# differential_op_amps.net
KiCad netlist of a schematic drawn in Altium Designer
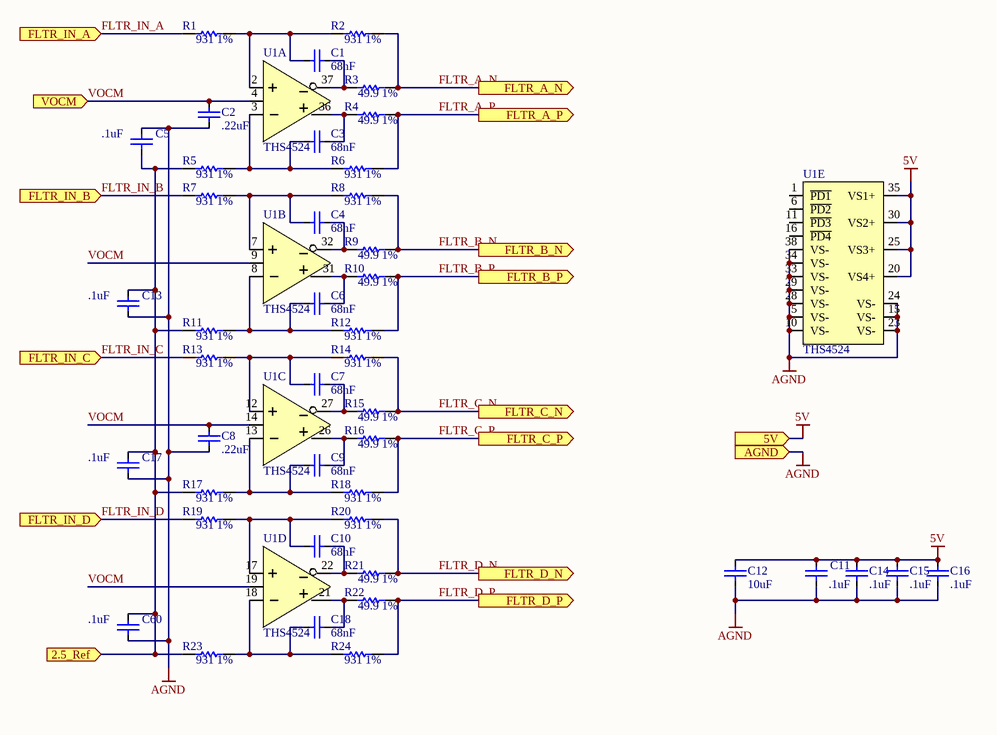
[diagram p0: differential_op_amps.SchDoc]

(export (version "E")
  (design (tool "Eeschema 10.0.6"))
  (components
    (comp (ref "C1")
      (value "68nF")
      (footprint "0603 (1608)")
      (fields
        (field (name "MANUFACTURER") "TDK")
        (field (name "PART NO.") "445-5096-1-ND")
        (field (name "Comment") "Capacitor")
      )
      (libsource (lib "SMT Chip") (part "Capacitor"))
    )
    (comp (ref "C2")
      (value ".22uF")
      (footprint "0603 (1608)")
      (fields
        (field (name "MANUFACTURER") "TDK")
        (field (name "PART NO.") "445-1318-1-ND")
        (field (name "Comment") "Capacitor")
      )
      (libsource (lib "SMT Chip") (part "Capacitor"))
    )
    (comp (ref "C3")
      (value "68nF")
      (footprint "0603 (1608)")
      (fields
        (field (name "MANUFACTURER") "TDK")
        (field (name "PART NO.") "445-5096-1-ND")
        (field (name "Comment") "Capacitor")
      )
      (libsource (lib "SMT Chip") (part "Capacitor"))
    )
    (comp (ref "C4")
      (value "68nF")
      (footprint "0603 (1608)")
      (fields
        (field (name "MANUFACTURER") "TDK")
        (field (name "PART NO.") "445-5096-1-ND")
        (field (name "Comment") "Capacitor")
      )
      (libsource (lib "SMT Chip") (part "Capacitor"))
    )
    (comp (ref "C5")
      (value ".1uF")
      (footprint "0603 (1608)")
      (fields
        (field (name "MANUFACTURER") "Murata")
        (field (name "PART NO.") "490-1524-1-ND")
        (field (name "Comment") "Capacitor")
      )
      (libsource (lib "SMT Chip") (part "Capacitor"))
    )
    (comp (ref "C6")
      (value "68nF")
      (footprint "0603 (1608)")
      (fields
        (field (name "MANUFACTURER") "TDK")
        (field (name "PART NO.") "445-5096-1-ND")
        (field (name "Comment") "Capacitor")
      )
      (libsource (lib "SMT Chip") (part "Capacitor"))
    )
    (comp (ref "C7")
      (value "68nF")
      (footprint "0603 (1608)")
      (fields
        (field (name "MANUFACTURER") "TDK")
        (field (name "PART NO.") "445-5096-1-ND")
        (field (name "Comment") "Capacitor")
      )
      (libsource (lib "SMT Chip") (part "Capacitor"))
    )
    (comp (ref "C8")
      (value ".22uF")
      (footprint "0603 (1608)")
      (fields
        (field (name "MANUFACTURER") "TDK")
        (field (name "PART NO.") "445-1318-1-ND")
        (field (name "Comment") "Capacitor")
      )
      (libsource (lib "SMT Chip") (part "Capacitor"))
    )
    (comp (ref "C9")
      (value "68nF")
      (footprint "0603 (1608)")
      (fields
        (field (name "MANUFACTURER") "TDK")
        (field (name "PART NO.") "445-5096-1-ND")
        (field (name "Comment") "Capacitor")
      )
      (libsource (lib "SMT Chip") (part "Capacitor"))
    )
    (comp (ref "C10")
      (value "68nF")
      (footprint "0603 (1608)")
      (fields
        (field (name "MANUFACTURER") "TDK")
        (field (name "PART NO.") "445-5096-1-ND")
        (field (name "Comment") "Capacitor")
      )
      (libsource (lib "SMT Chip") (part "Capacitor"))
    )
    (comp (ref "C11")
      (value ".1uF")
      (footprint "0603 (1608)")
      (fields
        (field (name "MANUFACTURER") "Murata")
        (field (name "PART NO.") "490-1524-1-ND")
        (field (name "Comment") "Capacitor")
      )
      (libsource (lib "SMT Chip") (part "Capacitor"))
    )
    (comp (ref "C12")
      (value "10uF")
      (footprint "0603 (1608)")
      (fields
        (field (name "MANUFACTURER") "Taiyo Yuden")
        (field (name "PART NO.") "587-2562-1-ND")
        (field (name "TOLERANCE") "20%")
      )
      (libsource (lib "SMT Chip") (part "Capacitor"))
    )
    (comp (ref "C13")
      (value ".1uF")
      (footprint "0603 (1608)")
      (fields
        (field (name "MANUFACTURER") "Murata")
        (field (name "PART NO.") "490-1524-1-ND")
        (field (name "Comment") "Capacitor")
      )
      (libsource (lib "SMT Chip") (part "Capacitor"))
    )
    (comp (ref "C14")
      (value ".1uF")
      (footprint "0603 (1608)")
      (fields
        (field (name "MANUFACTURER") "Murata")
        (field (name "PART NO.") "490-1524-1-ND")
        (field (name "Comment") "Capacitor")
      )
      (libsource (lib "SMT Chip") (part "Capacitor"))
    )
    (comp (ref "C15")
      (value ".1uF")
      (footprint "0603 (1608)")
      (fields
        (field (name "MANUFACTURER") "Murata")
        (field (name "PART NO.") "490-1524-1-ND")
        (field (name "Comment") "Capacitor")
      )
      (libsource (lib "SMT Chip") (part "Capacitor"))
    )
    (comp (ref "C16")
      (value ".1uF")
      (footprint "0603 (1608)")
      (fields
        (field (name "MANUFACTURER") "Murata")
        (field (name "PART NO.") "490-1524-1-ND")
        (field (name "Comment") "Capacitor")
      )
      (libsource (lib "SMT Chip") (part "Capacitor"))
    )
    (comp (ref "C17")
      (value ".1uF")
      (footprint "0603 (1608)")
      (fields
        (field (name "MANUFACTURER") "Murata")
        (field (name "PART NO.") "490-1524-1-ND")
        (field (name "Comment") "Capacitor")
      )
      (libsource (lib "SMT Chip") (part "Capacitor"))
    )
    (comp (ref "C18")
      (value "68nF")
      (footprint "0603 (1608)")
      (fields
        (field (name "MANUFACTURER") "TDK")
        (field (name "PART NO.") "445-5096-1-ND")
        (field (name "Comment") "Capacitor")
      )
      (libsource (lib "SMT Chip") (part "Capacitor"))
    )
    (comp (ref "C60")
      (value ".1uF")
      (footprint "0603 (1608)")
      (fields
        (field (name "MANUFACTURER") "Murata")
        (field (name "PART NO.") "490-1524-1-ND")
        (field (name "Comment") "Capacitor")
      )
      (libsource (lib "SMT Chip") (part "Capacitor"))
    )
    (comp (ref "R1")
      (value "931 1%")
      (footprint "0603 (1608)")
      (description "Resistor")
      (fields (field (name "PART NO.") "P931HCT-ND"))
      (libsource (lib "Miscellaneous Devices") (part "Res1"))
    )
    (comp (ref "R2")
      (value "931 1%")
      (footprint "0603 (1608)")
      (description "Resistor")
      (fields (field (name "PART NO.") "P931HCT-ND"))
      (libsource (lib "Miscellaneous Devices") (part "Res1"))
    )
    (comp (ref "R3")
      (value "49.9 1%")
      (footprint "0603 (1608)")
      (description "Resistor")
      (fields (field (name "PART NO.") "P49.9HCT-ND") (field (name "Comment") "931 1%"))
      (libsource (lib "Miscellaneous Devices") (part "Res1"))
    )
    (comp (ref "R4")
      (value "49.9 1%")
      (footprint "0603 (1608)")
      (description "Resistor")
      (fields (field (name "PART NO.") "P49.9HCT-ND") (field (name "Comment") "931 1%"))
      (libsource (lib "Miscellaneous Devices") (part "Res1"))
    )
    (comp (ref "R5")
      (value "931 1%")
      (footprint "0603 (1608)")
      (description "Resistor")
      (fields (field (name "PART NO.") "P931HCT-ND"))
      (libsource (lib "Miscellaneous Devices") (part "Res1"))
    )
    (comp (ref "R6")
      (value "931 1%")
      (footprint "0603 (1608)")
      (description "Resistor")
      (fields (field (name "PART NO.") "P931HCT-ND"))
      (libsource (lib "Miscellaneous Devices") (part "Res1"))
    )
    (comp (ref "R7")
      (value "931 1%")
      (footprint "0603 (1608)")
      (description "Resistor")
      (fields (field (name "PART NO.") "P931HCT-ND"))
      (libsource (lib "Miscellaneous Devices") (part "Res1"))
    )
    (comp (ref "R8")
      (value "931 1%")
      (footprint "0603 (1608)")
      (description "Resistor")
      (fields (field (name "PART NO.") "P931HCT-ND"))
      (libsource (lib "Miscellaneous Devices") (part "Res1"))
    )
    (comp (ref "R9")
      (value "49.9 1%")
      (footprint "0603 (1608)")
      (description "Resistor")
      (fields (field (name "PART NO.") "P49.9HCT-ND") (field (name "Comment") "931 1%"))
      (libsource (lib "Miscellaneous Devices") (part "Res1"))
    )
    (comp (ref "R10")
      (value "49.9 1%")
      (footprint "0603 (1608)")
      (description "Resistor")
      (fields (field (name "PART NO.") "P49.9HCT-ND") (field (name "Comment") "931 1%"))
      (libsource (lib "Miscellaneous Devices") (part "Res1"))
    )
    (comp (ref "R11")
      (value "931 1%")
      (footprint "0603 (1608)")
      (description "Resistor")
      (fields (field (name "PART NO.") "P931HCT-ND"))
      (libsource (lib "Miscellaneous Devices") (part "Res1"))
    )
    (comp (ref "R12")
      (value "931 1%")
      (footprint "0603 (1608)")
      (description "Resistor")
      (fields (field (name "PART NO.") "P931HCT-ND"))
      (libsource (lib "Miscellaneous Devices") (part "Res1"))
    )
    (comp (ref "R13")
      (value "931 1%")
      (footprint "0603 (1608)")
      (description "Resistor")
      (fields (field (name "PART NO.") "P931HCT-ND"))
      (libsource (lib "Miscellaneous Devices") (part "Res1"))
    )
    (comp (ref "R14")
      (value "931 1%")
      (footprint "0603 (1608)")
      (description "Resistor")
      (fields (field (name "PART NO.") "P931HCT-ND"))
      (libsource (lib "Miscellaneous Devices") (part "Res1"))
    )
    (comp (ref "R15")
      (value "49.9 1%")
      (footprint "0603 (1608)")
      (description "Resistor")
      (fields (field (name "PART NO.") "P49.9HCT-ND") (field (name "Comment") "931 1%"))
      (libsource (lib "Miscellaneous Devices") (part "Res1"))
    )
    (comp (ref "R16")
      (value "49.9 1%")
      (footprint "0603 (1608)")
      (description "Resistor")
      (fields (field (name "PART NO.") "P49.9HCT-ND") (field (name "Comment") "931 1%"))
      (libsource (lib "Miscellaneous Devices") (part "Res1"))
    )
    (comp (ref "R17")
      (value "931 1%")
      (footprint "0603 (1608)")
      (description "Resistor")
      (fields (field (name "PART NO.") "P931HCT-ND"))
      (libsource (lib "Miscellaneous Devices") (part "Res1"))
    )
    (comp (ref "R18")
      (value "931 1%")
      (footprint "0603 (1608)")
      (description "Resistor")
      (fields (field (name "PART NO.") "P931HCT-ND"))
      (libsource (lib "Miscellaneous Devices") (part "Res1"))
    )
    (comp (ref "R19")
      (value "931 1%")
      (footprint "0603 (1608)")
      (description "Resistor")
      (fields (field (name "PART NO.") "P931HCT-ND"))
      (libsource (lib "Miscellaneous Devices") (part "Res1"))
    )
    (comp (ref "R20")
      (value "931 1%")
      (footprint "0603 (1608)")
      (description "Resistor")
      (fields (field (name "PART NO.") "P931HCT-ND"))
      (libsource (lib "Miscellaneous Devices") (part "Res1"))
    )
    (comp (ref "R21")
      (value "49.9 1%")
      (footprint "0603 (1608)")
      (description "Resistor")
      (fields (field (name "PART NO.") "P49.9HCT-ND") (field (name "Comment") "931 1%"))
      (libsource (lib "Miscellaneous Devices") (part "Res1"))
    )
    (comp (ref "R22")
      (value "49.9 1%")
      (footprint "0603 (1608)")
      (description "Resistor")
      (fields (field (name "PART NO.") "P49.9HCT-ND") (field (name "Comment") "931 1%"))
      (libsource (lib "Miscellaneous Devices") (part "Res1"))
    )
    (comp (ref "R23")
      (value "931 1%")
      (footprint "0603 (1608)")
      (description "Resistor")
      (fields (field (name "PART NO.") "P931HCT-ND"))
      (libsource (lib "Miscellaneous Devices") (part "Res1"))
    )
    (comp (ref "R24")
      (value "931 1%")
      (footprint "0603 (1608)")
      (description "Resistor")
      (fields (field (name "PART NO.") "P931HCT-ND"))
      (libsource (lib "Miscellaneous Devices") (part "Res1"))
    )
    (comp (ref "U1")
      (value "THS4524")
      (footprint "TSSOP-38")
      (fields (field (name "PART NO.") "296-24315-1-ND"))
      (libsource (lib "imu") (part "THS4524"))
    )
  )
  (nets
    (net (code "1") (name "/2.5_Ref") (class "Default")
      (node (ref "C13") (pin "1") (pinfunction "1_1") (pintype "passive"))
      (node (ref "C17") (pin "1") (pinfunction "1_1") (pintype "passive"))
      (node (ref "C5") (pin "2") (pinfunction "2_2") (pintype "passive"))
      (node (ref "C60") (pin "1") (pinfunction "1_1") (pintype "passive"))
      (node (ref "R11") (pin "1") (pinfunction "1_1") (pintype "passive"))
      (node (ref "R17") (pin "1") (pinfunction "1_1") (pintype "passive"))
      (node (ref "R23") (pin "1") (pinfunction "1_1") (pintype "passive"))
      (node (ref "R5") (pin "1") (pinfunction "1_1") (pintype "passive"))
    )
    (net (code "2") (name "/FLTR_A_N") (class "Default")
      (node (ref "R2") (pin "2") (pinfunction "2_2") (pintype "passive"))
      (node (ref "R3") (pin "2") (pinfunction "2_2") (pintype "passive"))
    )
    (net (code "3") (name "/FLTR_A_P") (class "Default")
      (node (ref "R4") (pin "2") (pinfunction "2_2") (pintype "passive"))
      (node (ref "R6") (pin "2") (pinfunction "2_2") (pintype "passive"))
    )
    (net (code "4") (name "/FLTR_B_N") (class "Default")
      (node (ref "R8") (pin "2") (pinfunction "2_2") (pintype "passive"))
      (node (ref "R9") (pin "2") (pinfunction "2_2") (pintype "passive"))
    )
    (net (code "5") (name "/FLTR_B_P") (class "Default")
      (node (ref "R10") (pin "2") (pinfunction "2_2") (pintype "passive"))
      (node (ref "R12") (pin "2") (pinfunction "2_2") (pintype "passive"))
    )
    (net (code "6") (name "/FLTR_C_N") (class "Default")
      (node (ref "R14") (pin "2") (pinfunction "2_2") (pintype "passive"))
      (node (ref "R15") (pin "2") (pinfunction "2_2") (pintype "passive"))
    )
    (net (code "7") (name "/FLTR_C_P") (class "Default")
      (node (ref "R16") (pin "2") (pinfunction "2_2") (pintype "passive"))
      (node (ref "R18") (pin "2") (pinfunction "2_2") (pintype "passive"))
    )
    (net (code "8") (name "/FLTR_D_N") (class "Default")
      (node (ref "R20") (pin "2") (pinfunction "2_2") (pintype "passive"))
      (node (ref "R21") (pin "2") (pinfunction "2_2") (pintype "passive"))
    )
    (net (code "9") (name "/FLTR_D_P") (class "Default")
      (node (ref "R22") (pin "2") (pinfunction "2_2") (pintype "passive"))
      (node (ref "R24") (pin "2") (pinfunction "2_2") (pintype "passive"))
    )
    (net (code "10") (name "/FLTR_IN_A") (class "Default")
      (node (ref "R1") (pin "1") (pinfunction "1_1") (pintype "passive"))
    )
    (net (code "11") (name "/FLTR_IN_B") (class "Default")
      (node (ref "R7") (pin "1") (pinfunction "1_1") (pintype "passive"))
    )
    (net (code "12") (name "/FLTR_IN_C") (class "Default")
      (node (ref "R13") (pin "1") (pinfunction "1_1") (pintype "passive"))
    )
    (net (code "13") (name "/FLTR_IN_D") (class "Default")
      (node (ref "R19") (pin "1") (pinfunction "1_1") (pintype "passive"))
    )
    (net (code "14") (name "/VOCM") (class "Default")
      (node (ref "C2") (pin "2") (pinfunction "2_2") (pintype "passive"))
      (node (ref "C8") (pin "2") (pinfunction "2_2") (pintype "passive"))
      (node (ref "U1") (pin "14") (pinfunction "VOCM3_14") (pintype "passive"))
      (node (ref "U1") (pin "19") (pinfunction "VOCM4_19") (pintype "passive"))
      (node (ref "U1") (pin "4") (pinfunction "VOCM1_4") (pintype "passive"))
      (node (ref "U1") (pin "9") (pinfunction "VOCM2_9") (pintype "passive"))
    )
    (net (code "15") (name "5V") (class "Default")
      (node (ref "C11") (pin "1") (pinfunction "1_1") (pintype "passive"))
      (node (ref "C12") (pin "1") (pinfunction "1_1") (pintype "passive"))
      (node (ref "C14") (pin "1") (pinfunction "1_1") (pintype "passive"))
      (node (ref "C15") (pin "1") (pinfunction "1_1") (pintype "passive"))
      (node (ref "C16") (pin "1") (pinfunction "1_1") (pintype "passive"))
      (node (ref "U1") (pin "20") (pinfunction "VS4+_20") (pintype "passive"))
      (node (ref "U1") (pin "25") (pinfunction "VS3+_25") (pintype "passive"))
      (node (ref "U1") (pin "30") (pinfunction "VS2+_30") (pintype "passive"))
      (node (ref "U1") (pin "35") (pinfunction "VS1+_35") (pintype "passive"))
    )
    (net (code "16") (name "AGND") (class "Default")
      (node (ref "C11") (pin "2") (pinfunction "2_2") (pintype "passive"))
      (node (ref "C12") (pin "2") (pinfunction "2_2") (pintype "passive"))
      (node (ref "C13") (pin "2") (pinfunction "2_2") (pintype "passive"))
      (node (ref "C14") (pin "2") (pinfunction "2_2") (pintype "passive"))
      (node (ref "C15") (pin "2") (pinfunction "2_2") (pintype "passive"))
      (node (ref "C16") (pin "2") (pinfunction "2_2") (pintype "passive"))
      (node (ref "C17") (pin "2") (pinfunction "2_2") (pintype "passive"))
      (node (ref "C2") (pin "1") (pinfunction "1_1") (pintype "passive"))
      (node (ref "C5") (pin "1") (pinfunction "1_1") (pintype "passive"))
      (node (ref "C60") (pin "2") (pinfunction "2_2") (pintype "passive"))
      (node (ref "C8") (pin "1") (pinfunction "1_1") (pintype "passive"))
      (node (ref "U1") (pin "10") (pinfunction "VS-_10") (pintype "passive"))
      (node (ref "U1") (pin "15") (pinfunction "VS-_15") (pintype "passive"))
      (node (ref "U1") (pin "23") (pinfunction "VS-_23") (pintype "passive"))
      (node (ref "U1") (pin "24") (pinfunction "VS-_24") (pintype "passive"))
      (node (ref "U1") (pin "28") (pinfunction "VS-_28") (pintype "passive"))
      (node (ref "U1") (pin "29") (pinfunction "VS-_29") (pintype "passive"))
      (node (ref "U1") (pin "33") (pinfunction "VS-_33") (pintype "passive"))
      (node (ref "U1") (pin "34") (pinfunction "VS-_34") (pintype "passive"))
      (node (ref "U1") (pin "38") (pinfunction "VS-_38") (pintype "passive"))
      (node (ref "U1") (pin "5") (pinfunction "VS-_5") (pintype "passive"))
    )
    (net (code "17") (name "Net-(U1A-VIN1+)") (class "Default")
      (node (ref "C1") (pin "2") (pinfunction "2_2") (pintype "passive"))
      (node (ref "R1") (pin "2") (pinfunction "2_2") (pintype "passive"))
      (node (ref "R2") (pin "1") (pinfunction "1_1") (pintype "passive"))
      (node (ref "U1") (pin "2") (pinfunction "VIN1+_2") (pintype "passive"))
    )
    (net (code "18") (name "Net-(U1A-VIN1-)") (class "Default")
      (node (ref "C3") (pin "2") (pinfunction "2_2") (pintype "passive"))
      (node (ref "R5") (pin "2") (pinfunction "2_2") (pintype "passive"))
      (node (ref "R6") (pin "1") (pinfunction "1_1") (pintype "passive"))
      (node (ref "U1") (pin "3") (pinfunction "VIN1-_3") (pintype "passive"))
    )
    (net (code "19") (name "Net-(U1A-VOUT1+)") (class "Default")
      (node (ref "C3") (pin "1") (pinfunction "1_1") (pintype "passive"))
      (node (ref "R4") (pin "1") (pinfunction "1_1") (pintype "passive"))
      (node (ref "U1") (pin "36") (pinfunction "VOUT1+_36") (pintype "passive"))
    )
    (net (code "20") (name "Net-(U1A-VOUT1-)") (class "Default")
      (node (ref "C1") (pin "1") (pinfunction "1_1") (pintype "passive"))
      (node (ref "R3") (pin "1") (pinfunction "1_1") (pintype "passive"))
      (node (ref "U1") (pin "37") (pinfunction "VOUT1-_37") (pintype "passive"))
    )
    (net (code "21") (name "Net-(U1B-VIN2+)") (class "Default")
      (node (ref "C4") (pin "2") (pinfunction "2_2") (pintype "passive"))
      (node (ref "R7") (pin "2") (pinfunction "2_2") (pintype "passive"))
      (node (ref "R8") (pin "1") (pinfunction "1_1") (pintype "passive"))
      (node (ref "U1") (pin "7") (pinfunction "VIN2+_7") (pintype "passive"))
    )
    (net (code "22") (name "Net-(U1B-VIN2-)") (class "Default")
      (node (ref "C6") (pin "2") (pinfunction "2_2") (pintype "passive"))
      (node (ref "R11") (pin "2") (pinfunction "2_2") (pintype "passive"))
      (node (ref "R12") (pin "1") (pinfunction "1_1") (pintype "passive"))
      (node (ref "U1") (pin "8") (pinfunction "VIN2-_8") (pintype "passive"))
    )
    (net (code "23") (name "Net-(U1B-VOUT2+)") (class "Default")
      (node (ref "C6") (pin "1") (pinfunction "1_1") (pintype "passive"))
      (node (ref "R10") (pin "1") (pinfunction "1_1") (pintype "passive"))
      (node (ref "U1") (pin "31") (pinfunction "VOUT2+_31") (pintype "passive"))
    )
    (net (code "24") (name "Net-(U1B-VOUT2-)") (class "Default")
      (node (ref "C4") (pin "1") (pinfunction "1_1") (pintype "passive"))
      (node (ref "R9") (pin "1") (pinfunction "1_1") (pintype "passive"))
      (node (ref "U1") (pin "32") (pinfunction "VOUT2-_32") (pintype "passive"))
    )
    (net (code "25") (name "Net-(U1C-VIN3+)") (class "Default")
      (node (ref "C7") (pin "2") (pinfunction "2_2") (pintype "passive"))
      (node (ref "R13") (pin "2") (pinfunction "2_2") (pintype "passive"))
      (node (ref "R14") (pin "1") (pinfunction "1_1") (pintype "passive"))
      (node (ref "U1") (pin "12") (pinfunction "VIN3+_12") (pintype "passive"))
    )
    (net (code "26") (name "Net-(U1C-VIN3-)") (class "Default")
      (node (ref "C9") (pin "2") (pinfunction "2_2") (pintype "passive"))
      (node (ref "R17") (pin "2") (pinfunction "2_2") (pintype "passive"))
      (node (ref "R18") (pin "1") (pinfunction "1_1") (pintype "passive"))
      (node (ref "U1") (pin "13") (pinfunction "VIN3-_13") (pintype "passive"))
    )
    (net (code "27") (name "Net-(U1C-VOUT3+)") (class "Default")
      (node (ref "C9") (pin "1") (pinfunction "1_1") (pintype "passive"))
      (node (ref "R16") (pin "1") (pinfunction "1_1") (pintype "passive"))
      (node (ref "U1") (pin "26") (pinfunction "VOUT3+_26") (pintype "passive"))
    )
    (net (code "28") (name "Net-(U1C-VOUT3-)") (class "Default")
      (node (ref "C7") (pin "1") (pinfunction "1_1") (pintype "passive"))
      (node (ref "R15") (pin "1") (pinfunction "1_1") (pintype "passive"))
      (node (ref "U1") (pin "27") (pinfunction "VOUT3-_27") (pintype "passive"))
    )
    (net (code "29") (name "Net-(U1D-VIN4+)") (class "Default")
      (node (ref "C10") (pin "2") (pinfunction "2_2") (pintype "passive"))
      (node (ref "R19") (pin "2") (pinfunction "2_2") (pintype "passive"))
      (node (ref "R20") (pin "1") (pinfunction "1_1") (pintype "passive"))
      (node (ref "U1") (pin "17") (pinfunction "VIN4+_17") (pintype "passive"))
    )
    (net (code "30") (name "Net-(U1D-VIN4-)") (class "Default")
      (node (ref "C18") (pin "2") (pinfunction "2_2") (pintype "passive"))
      (node (ref "R23") (pin "2") (pinfunction "2_2") (pintype "passive"))
      (node (ref "R24") (pin "1") (pinfunction "1_1") (pintype "passive"))
      (node (ref "U1") (pin "18") (pinfunction "VIN4-_18") (pintype "passive"))
    )
    (net (code "31") (name "Net-(U1D-VOUT4+)") (class "Default")
      (node (ref "C18") (pin "1") (pinfunction "1_1") (pintype "passive"))
      (node (ref "R22") (pin "1") (pinfunction "1_1") (pintype "passive"))
      (node (ref "U1") (pin "21") (pinfunction "VOUT4+_21") (pintype "passive"))
    )
    (net (code "32") (name "Net-(U1D-VOUT4_)") (class "Default")
      (node (ref "C10") (pin "1") (pinfunction "1_1") (pintype "passive"))
      (node (ref "R21") (pin "1") (pinfunction "1_1") (pintype "passive"))
      (node (ref "U1") (pin "22") (pinfunction "VOUT4__22") (pintype "passive"))
    )
    (net (code "33") (name "unconnected-(U1E-~{PD1}-Pad1)") (class "Default")
      (node (ref "U1") (pin "1") (pinfunction "~{PD1}_1") (pintype "passive"))
    )
    (net (code "34") (name "unconnected-(U1E-~{PD2}-Pad6)") (class "Default")
      (node (ref "U1") (pin "6") (pinfunction "~{PD2}_6") (pintype "passive"))
    )
    (net (code "35") (name "unconnected-(U1E-~{PD3}-Pad11)") (class "Default")
      (node (ref "U1") (pin "11") (pinfunction "~{PD3}_11") (pintype "passive"))
    )
    (net (code "36") (name "unconnected-(U1E-~{PD4}-Pad16)") (class "Default")
      (node (ref "U1") (pin "16") (pinfunction "~{PD4}_16") (pintype "passive"))
    )
  )
)
